# smd.net
KiCad netlist of a schematic drawn in EAGLE
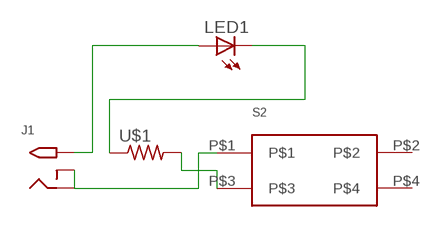
[diagram p0: schematic, sheet 1]

(export (version "E")
  (design (tool "Eeschema 10.0.6"))
  (components
    (comp (ref "J1")
      (value "2.1MMJACKTHM")
      (footprint "eagle-import:PJ-102A")
      (libsource (lib "eagle-import") (part "2.1MMJACKTHM"))
    )
    (comp (ref "LED1")
      (value "LED5MM")
      (footprint "eagle-import:LED5MM")
      (libsource (lib "eagle-import") (part "LED5MM"))
    )
    (comp (ref "S2")
      (value "MYBUTTON")
      (footprint "eagle-import:BUTTON-TACTILE-SQUARE")
      (libsource (lib "eagle-import") (part "MYBUTTON"))
    )
    (comp (ref "U$1")
      (value "RESISTORTH-1/4W-CARBON")
      (footprint "eagle-import:RESAD1160W55L680D260_HS")
      (libsource (lib "eagle-import") (part "RESISTORTH-1/4W-CARBON"))
    )
  )
  (nets
    (net (code "1") (name "Net-(J1-PadRING)") (class "Default")
      (node (ref "J1") (pin "RING") (pinfunction "RING_RING") (pintype "bidirectional"))
      (node (ref "J1") (pin "RING_SW") (pinfunction "RING_SW_RING_SW") (pintype "bidirectional"))
      (node (ref "S2") (pin "P$1") (pinfunction "P$1_P$1") (pintype "bidirectional"))
    )
    (net (code "2") (name "Net-(J1-PadTIP)") (class "Default")
      (node (ref "J1") (pin "TIP") (pinfunction "TIP_TIP") (pintype "bidirectional"))
      (node (ref "LED1") (pin "A") (pinfunction "A_A") (pintype "passive"))
    )
    (net (code "3") (name "Net-(LED1-C)") (class "Default")
      (node (ref "LED1") (pin "K") (pinfunction "C_K") (pintype "passive"))
      (node (ref "U$1") (pin "1") (pinfunction "1_1") (pintype "passive"))
    )
    (net (code "4") (name "Net-(S2-PadP$3)") (class "Default")
      (node (ref "S2") (pin "P$3") (pinfunction "P$3_P$3") (pintype "bidirectional"))
      (node (ref "U$1") (pin "2") (pinfunction "2_2") (pintype "passive"))
    )
    (net (code "5") (name "unconnected-(S2-PadP$2)") (class "Default")
      (node (ref "S2") (pin "P$2") (pinfunction "P$2_P$2") (pintype "bidirectional"))
    )
    (net (code "6") (name "unconnected-(S2-PadP$4)") (class "Default")
      (node (ref "S2") (pin "P$4") (pinfunction "P$4_P$4") (pintype "bidirectional"))
    )
  )
)
